# AD7173.net
KiCad netlist of a schematic drawn in EAGLE
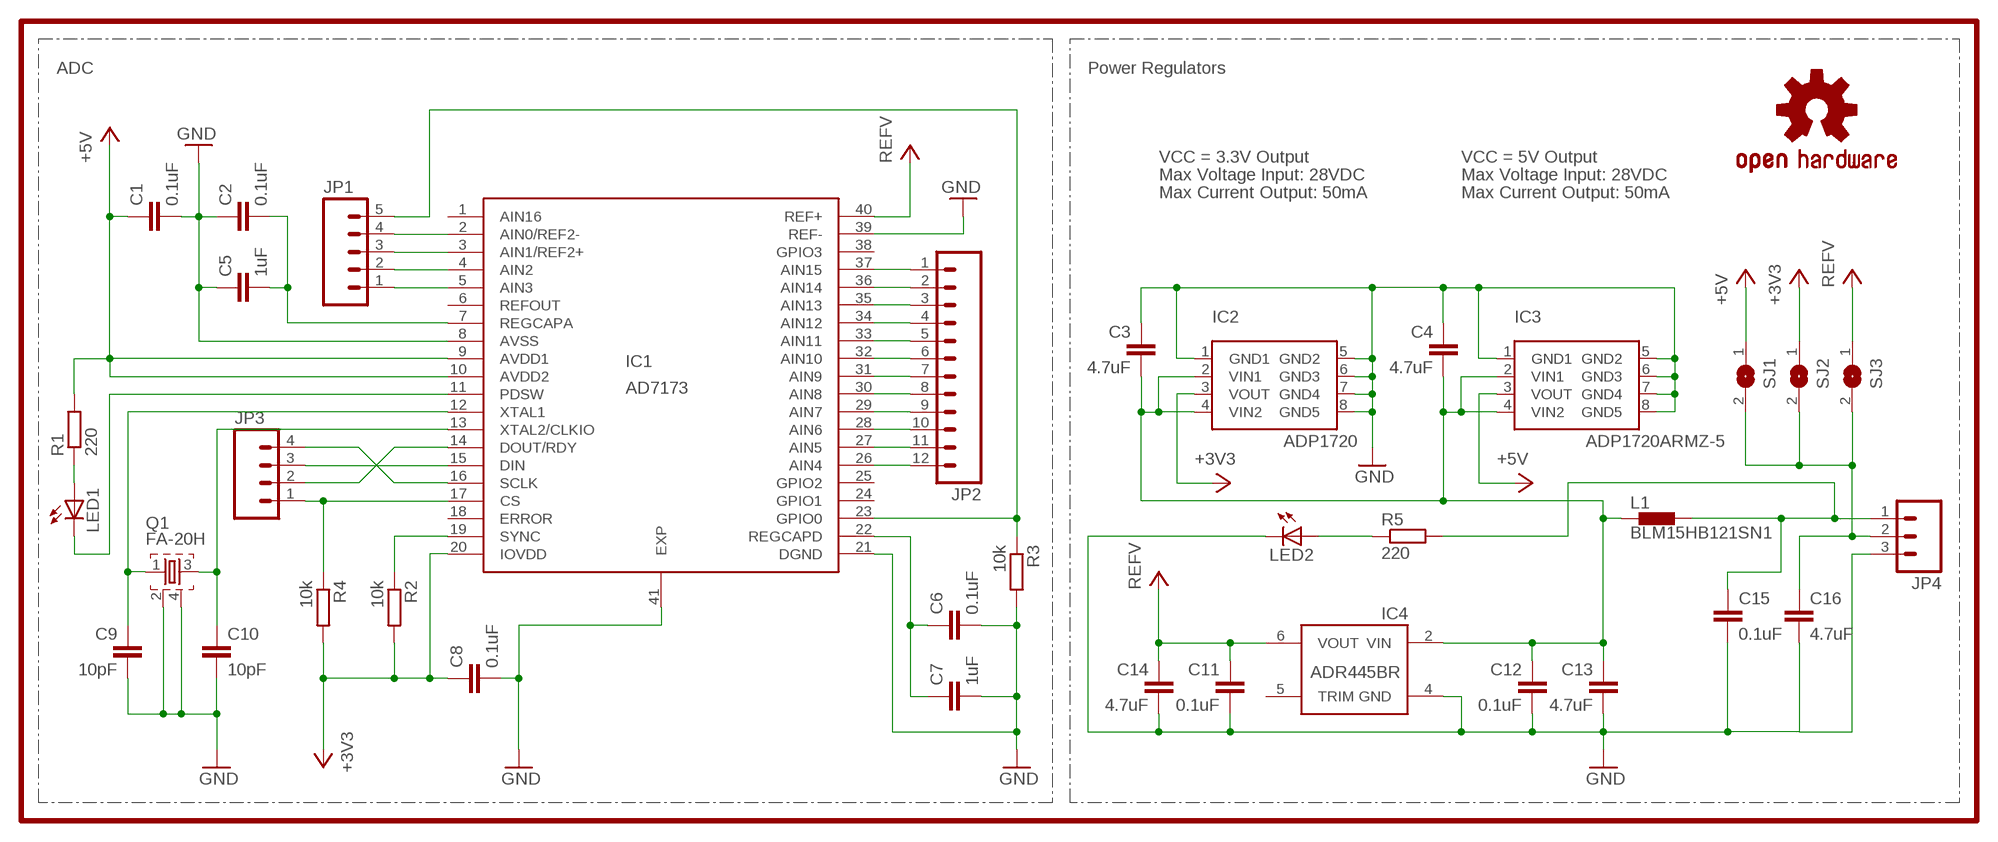
[diagram p0: schematic, sheet 1]

(export (version "E")
  (design (tool "Eeschema 10.0.6"))
  (components
    (comp (ref "C1")
      (value "0.1uF")
      (footprint "eagle-import:C0402")
      (libsource (lib "eagle-import") (part "C-EUC0402"))
    )
    (comp (ref "C2")
      (value "0.1uF")
      (footprint "eagle-import:C0402")
      (libsource (lib "eagle-import") (part "C-EUC0402"))
    )
    (comp (ref "C3")
      (value "4.7uF")
      (footprint "eagle-import:C0402")
      (libsource (lib "eagle-import") (part "C-EUC0402"))
    )
    (comp (ref "C4")
      (value "4.7uF")
      (footprint "eagle-import:C0402")
      (libsource (lib "eagle-import") (part "C-EUC0402"))
    )
    (comp (ref "C5")
      (value "1uF")
      (footprint "eagle-import:C0402")
      (libsource (lib "eagle-import") (part "C-EUC0402"))
    )
    (comp (ref "C6")
      (value "0.1uF")
      (footprint "eagle-import:C0402")
      (libsource (lib "eagle-import") (part "C-EUC0402"))
    )
    (comp (ref "C7")
      (value "1uF")
      (footprint "eagle-import:C0402")
      (libsource (lib "eagle-import") (part "C-EUC0402"))
    )
    (comp (ref "C8")
      (value "0.1uF")
      (footprint "eagle-import:C0402")
      (libsource (lib "eagle-import") (part "C-EUC0402"))
    )
    (comp (ref "C9")
      (value "10pF")
      (footprint "eagle-import:C0402")
      (libsource (lib "eagle-import") (part "C-EUC0402"))
    )
    (comp (ref "C10")
      (value "10pF")
      (footprint "eagle-import:C0402")
      (libsource (lib "eagle-import") (part "C-EUC0402"))
    )
    (comp (ref "C11")
      (value "0.1uF")
      (footprint "eagle-import:C0402")
      (libsource (lib "eagle-import") (part "C-EUC0402"))
    )
    (comp (ref "C12")
      (value "0.1uF")
      (footprint "eagle-import:C0402")
      (libsource (lib "eagle-import") (part "C-EUC0402"))
    )
    (comp (ref "C13")
      (value "4.7uF")
      (footprint "eagle-import:C0402")
      (libsource (lib "eagle-import") (part "C-EUC0402"))
    )
    (comp (ref "C14")
      (value "4.7uF")
      (footprint "eagle-import:C0402")
      (libsource (lib "eagle-import") (part "C-EUC0402"))
    )
    (comp (ref "C15")
      (value "0.1uF")
      (footprint "eagle-import:C0402")
      (libsource (lib "eagle-import") (part "C-EUC0402"))
    )
    (comp (ref "C16")
      (value "4.7uF")
      (footprint "eagle-import:C0402")
      (libsource (lib "eagle-import") (part "C-EUC0402"))
    )
    (comp (ref "IC1")
      (value "AD7173")
      (footprint "eagle-import:LFCSP_WQ6X6MM")
      (fields (field (name "MPN") "MRF24J40-I/ML"))
      (libsource (lib "eagle-import") (part "AD7173"))
    )
    (comp (ref "IC2")
      (value "ADP1720")
      (footprint "eagle-import:MSOP08")
      (libsource (lib "eagle-import") (part "POWER"))
    )
    (comp (ref "IC3")
      (value "ADP1720ARMZ-5")
      (footprint "eagle-import:MSOP08")
      (libsource (lib "eagle-import") (part "POWER"))
    )
    (comp (ref "IC4")
      (value "ADR445BR")
      (footprint "eagle-import:SO8")
      (libsource (lib "eagle-import") (part "ADR44R5B"))
    )
    (comp (ref "JP1")
      (value "M05PTH")
      (footprint "eagle-import:1X05")
      (libsource (lib "eagle-import") (part "M05PTH"))
    )
    (comp (ref "JP2")
      (value "M12PTH")
      (footprint "eagle-import:1X12")
      (libsource (lib "eagle-import") (part "M12PTH"))
    )
    (comp (ref "JP3")
      (value "M04PTH")
      (footprint "eagle-import:1X04")
      (libsource (lib "eagle-import") (part "M04PTH"))
    )
    (comp (ref "JP4")
      (value "M03PTH")
      (footprint "eagle-import:1X03")
      (libsource (lib "eagle-import") (part "M03PTH"))
    )
    (comp (ref "L1")
      (value "BLM15HB121SN1")
      (footprint "eagle-import:0402")
      (libsource (lib "eagle-import") (part "BLM15HB121SN1"))
    )
    (comp (ref "LED1")
      (value "LEDCHIP-LED0603")
      (footprint "eagle-import:CHIP-LED0603")
      (libsource (lib "eagle-import") (part "LEDCHIP-LED0603"))
    )
    (comp (ref "LED2")
      (value "LEDCHIP-LED0603")
      (footprint "eagle-import:CHIP-LED0603")
      (libsource (lib "eagle-import") (part "LEDCHIP-LED0603"))
    )
    (comp (ref "LOGO1")
      (value "OSHW-LOGOS")
      (footprint "eagle-import:OSHW-LOGO-S")
      (libsource (lib "eagle-import") (part "OSHW-LOGOS"))
    )
    (comp (ref "Q1")
      (value "FA-20H")
      (footprint "eagle-import:FA-20H")
      (libsource (lib "eagle-import") (part "FA-20H"))
    )
    (comp (ref "R1")
      (value "220")
      (footprint "eagle-import:R0402")
      (libsource (lib "eagle-import") (part "R-EU_R0402"))
    )
    (comp (ref "R2")
      (value "10k")
      (footprint "eagle-import:R0402")
      (libsource (lib "eagle-import") (part "R-EU_R0402"))
    )
    (comp (ref "R3")
      (value "10k")
      (footprint "eagle-import:R0402")
      (libsource (lib "eagle-import") (part "R-EU_R0402"))
    )
    (comp (ref "R4")
      (value "10k")
      (footprint "eagle-import:R0402")
      (libsource (lib "eagle-import") (part "R-EU_R0402"))
    )
    (comp (ref "R5")
      (value "220")
      (footprint "eagle-import:R0402")
      (libsource (lib "eagle-import") (part "R-EU_R0402"))
    )
    (comp (ref "SJ1") (value "SJ") (footprint "eagle-import:SJ") (libsource (lib "eagle-import") (part "SJ")))
    (comp (ref "SJ2") (value "SJ") (footprint "eagle-import:SJ") (libsource (lib "eagle-import") (part "SJ")))
    (comp (ref "SJ3") (value "SJ") (footprint "eagle-import:SJ") (libsource (lib "eagle-import") (part "SJ")))
  )
  (nets
    (net (code "1") (name "+3V3") (class "Default")
      (node (ref "C8") (pin "1") (pinfunction "1_1") (pintype "passive"))
      (node (ref "IC1") (pin "20") (pinfunction "IOVDD_20") (pintype "input"))
      (node (ref "IC2") (pin "3") (pinfunction "VOUT_3") (pintype "output"))
      (node (ref "R2") (pin "2") (pinfunction "2_2") (pintype "passive"))
      (node (ref "R4") (pin "2") (pinfunction "2_2") (pintype "passive"))
      (node (ref "SJ2") (pin "1") (pinfunction "1_1") (pintype "passive"))
    )
    (net (code "2") (name "+5V") (class "Default")
      (node (ref "C1") (pin "1") (pinfunction "1_1") (pintype "passive"))
      (node (ref "IC1") (pin "10") (pinfunction "AVDD2_10") (pintype "input"))
      (node (ref "IC1") (pin "9") (pinfunction "AVDD1_9") (pintype "input"))
      (node (ref "IC3") (pin "3") (pinfunction "VOUT_3") (pintype "output"))
      (node (ref "R1") (pin "2") (pinfunction "2_2") (pintype "passive"))
      (node (ref "SJ1") (pin "1") (pinfunction "1_1") (pintype "passive"))
    )
    (net (code "3") (name "GND") (class "Default")
      (node (ref "C1") (pin "2") (pinfunction "2_2") (pintype "passive"))
      (node (ref "C10") (pin "2") (pinfunction "2_2") (pintype "passive"))
      (node (ref "C11") (pin "2") (pinfunction "2_2") (pintype "passive"))
      (node (ref "C12") (pin "2") (pinfunction "2_2") (pintype "passive"))
      (node (ref "C13") (pin "2") (pinfunction "2_2") (pintype "passive"))
      (node (ref "C14") (pin "2") (pinfunction "2_2") (pintype "passive"))
      (node (ref "C15") (pin "2") (pinfunction "2_2") (pintype "passive"))
      (node (ref "C16") (pin "2") (pinfunction "2_2") (pintype "passive"))
      (node (ref "C2") (pin "1") (pinfunction "1_1") (pintype "passive"))
      (node (ref "C3") (pin "1") (pinfunction "1_1") (pintype "passive"))
      (node (ref "C4") (pin "1") (pinfunction "1_1") (pintype "passive"))
      (node (ref "C5") (pin "1") (pinfunction "1_1") (pintype "passive"))
      (node (ref "C6") (pin "2") (pinfunction "2_2") (pintype "passive"))
      (node (ref "C7") (pin "2") (pinfunction "2_2") (pintype "passive"))
      (node (ref "C8") (pin "2") (pinfunction "2_2") (pintype "passive"))
      (node (ref "C9") (pin "2") (pinfunction "2_2") (pintype "passive"))
      (node (ref "IC1") (pin "21") (pinfunction "DGND_21") (pintype "input"))
      (node (ref "IC1") (pin "39") (pinfunction "REF-_39") (pintype "input"))
      (node (ref "IC1") (pin "41") (pinfunction "EXP_41") (pintype "output"))
      (node (ref "IC1") (pin "8") (pinfunction "AVSS_8") (pintype "input"))
      (node (ref "IC2") (pin "1") (pinfunction "GND1_1") (pintype "power_in"))
      (node (ref "IC2") (pin "5") (pinfunction "GND2_5") (pintype "power_in"))
      (node (ref "IC2") (pin "6") (pinfunction "GND3_6") (pintype "power_in"))
      (node (ref "IC2") (pin "7") (pinfunction "GND4_7") (pintype "power_in"))
      (node (ref "IC2") (pin "8") (pinfunction "GND5_8") (pintype "power_in"))
      (node (ref "IC3") (pin "1") (pinfunction "GND1_1") (pintype "power_in"))
      (node (ref "IC3") (pin "5") (pinfunction "GND2_5") (pintype "power_in"))
      (node (ref "IC3") (pin "6") (pinfunction "GND3_6") (pintype "power_in"))
      (node (ref "IC3") (pin "7") (pinfunction "GND4_7") (pintype "power_in"))
      (node (ref "IC3") (pin "8") (pinfunction "GND5_8") (pintype "power_in"))
      (node (ref "IC4") (pin "4") (pinfunction "GND_4") (pintype "power_in"))
      (node (ref "JP4") (pin "3") (pinfunction "3_3") (pintype "passive"))
      (node (ref "LED2") (pin "C") (pinfunction "C_C") (pintype "passive"))
      (node (ref "Q1") (pin "2") (pinfunction "2_2") (pintype "passive"))
      (node (ref "Q1") (pin "4") (pinfunction "4_4") (pintype "passive"))
      (node (ref "R3") (pin "2") (pinfunction "2_2") (pintype "passive"))
    )
    (net (code "4") (name "Net-(C15-Pad1)") (class "Default")
      (node (ref "C15") (pin "1") (pinfunction "1_1") (pintype "passive"))
      (node (ref "JP4") (pin "1") (pinfunction "1_1") (pintype "passive"))
      (node (ref "L1") (pin "2") (pinfunction "2_2") (pintype "passive"))
      (node (ref "R5") (pin "2") (pinfunction "2_2") (pintype "passive"))
    )
    (net (code "5") (name "Net-(C16-Pad1)") (class "Default")
      (node (ref "C16") (pin "1") (pinfunction "1_1") (pintype "passive"))
      (node (ref "JP4") (pin "2") (pinfunction "2_2") (pintype "passive"))
      (node (ref "SJ1") (pin "2") (pinfunction "2_2") (pintype "passive"))
      (node (ref "SJ2") (pin "2") (pinfunction "2_2") (pintype "passive"))
      (node (ref "SJ3") (pin "2") (pinfunction "2_2") (pintype "passive"))
    )
    (net (code "6") (name "Net-(IC1-AIN0{slash}REF2-)") (class "Default")
      (node (ref "IC1") (pin "2") (pinfunction "AIN0/REF2-_2") (pintype "input"))
      (node (ref "JP1") (pin "4") (pinfunction "4_4") (pintype "passive"))
    )
    (net (code "7") (name "Net-(IC1-AIN1{slash}REF2+)") (class "Default")
      (node (ref "IC1") (pin "3") (pinfunction "AIN1/REF2+_3") (pintype "input"))
      (node (ref "JP1") (pin "3") (pinfunction "3_3") (pintype "passive"))
    )
    (net (code "8") (name "Net-(IC1-AIN2)") (class "Default")
      (node (ref "IC1") (pin "4") (pinfunction "AIN2_4") (pintype "input"))
      (node (ref "JP1") (pin "2") (pinfunction "2_2") (pintype "passive"))
    )
    (net (code "9") (name "Net-(IC1-AIN3)") (class "Default")
      (node (ref "IC1") (pin "5") (pinfunction "AIN3_5") (pintype "input"))
      (node (ref "JP1") (pin "1") (pinfunction "1_1") (pintype "passive"))
    )
    (net (code "10") (name "Net-(IC1-AIN4)") (class "Default")
      (node (ref "IC1") (pin "26") (pinfunction "AIN4_26") (pintype "input"))
      (node (ref "JP2") (pin "12") (pinfunction "12_12") (pintype "passive"))
    )
    (net (code "11") (name "Net-(IC1-AIN5)") (class "Default")
      (node (ref "IC1") (pin "27") (pinfunction "AIN5_27") (pintype "input"))
      (node (ref "JP2") (pin "11") (pinfunction "11_11") (pintype "passive"))
    )
    (net (code "12") (name "Net-(IC1-AIN6)") (class "Default")
      (node (ref "IC1") (pin "28") (pinfunction "AIN6_28") (pintype "input"))
      (node (ref "JP2") (pin "10") (pinfunction "10_10") (pintype "passive"))
    )
    (net (code "13") (name "Net-(IC1-AIN7)") (class "Default")
      (node (ref "IC1") (pin "29") (pinfunction "AIN7_29") (pintype "input"))
      (node (ref "JP2") (pin "9") (pinfunction "9_9") (pintype "passive"))
    )
    (net (code "14") (name "Net-(IC1-AIN8)") (class "Default")
      (node (ref "IC1") (pin "30") (pinfunction "AIN8_30") (pintype "input"))
      (node (ref "JP2") (pin "8") (pinfunction "8_8") (pintype "passive"))
    )
    (net (code "15") (name "Net-(IC1-AIN9)") (class "Default")
      (node (ref "IC1") (pin "31") (pinfunction "AIN9_31") (pintype "input"))
      (node (ref "JP2") (pin "7") (pinfunction "7_7") (pintype "passive"))
    )
    (net (code "16") (name "Net-(IC1-AIN10)") (class "Default")
      (node (ref "IC1") (pin "32") (pinfunction "AIN10_32") (pintype "input"))
      (node (ref "JP2") (pin "6") (pinfunction "6_6") (pintype "passive"))
    )
    (net (code "17") (name "Net-(IC1-AIN11)") (class "Default")
      (node (ref "IC1") (pin "33") (pinfunction "AIN11_33") (pintype "input"))
      (node (ref "JP2") (pin "5") (pinfunction "5_5") (pintype "passive"))
    )
    (net (code "18") (name "Net-(IC1-AIN12)") (class "Default")
      (node (ref "IC1") (pin "34") (pinfunction "AIN12_34") (pintype "input"))
      (node (ref "JP2") (pin "4") (pinfunction "4_4") (pintype "passive"))
    )
    (net (code "19") (name "Net-(IC1-AIN13)") (class "Default")
      (node (ref "IC1") (pin "35") (pinfunction "AIN13_35") (pintype "input"))
      (node (ref "JP2") (pin "3") (pinfunction "3_3") (pintype "passive"))
    )
    (net (code "20") (name "Net-(IC1-AIN14)") (class "Default")
      (node (ref "IC1") (pin "36") (pinfunction "AIN14_36") (pintype "input"))
      (node (ref "JP2") (pin "2") (pinfunction "2_2") (pintype "passive"))
    )
    (net (code "21") (name "Net-(IC1-AIN15)") (class "Default")
      (node (ref "IC1") (pin "37") (pinfunction "AIN15_37") (pintype "input"))
      (node (ref "JP2") (pin "1") (pinfunction "1_1") (pintype "passive"))
    )
    (net (code "22") (name "Net-(IC1-CS)") (class "Default")
      (node (ref "IC1") (pin "17") (pinfunction "CS_17") (pintype "input"))
      (node (ref "JP3") (pin "1") (pinfunction "1_1") (pintype "passive"))
      (node (ref "R4") (pin "1") (pinfunction "1_1") (pintype "passive"))
    )
    (net (code "23") (name "Net-(IC1-DIN)") (class "Default")
      (node (ref "IC1") (pin "15") (pinfunction "DIN_15") (pintype "input"))
      (node (ref "JP3") (pin "3") (pinfunction "3_3") (pintype "passive"))
    )
    (net (code "24") (name "Net-(IC1-DOUT{slash}RDY)") (class "Default")
      (node (ref "IC1") (pin "14") (pinfunction "DOUT/RDY_14") (pintype "output"))
      (node (ref "JP3") (pin "2") (pinfunction "2_2") (pintype "passive"))
    )
    (net (code "25") (name "Net-(IC1-GPIO0)") (class "Default")
      (node (ref "IC1") (pin "23") (pinfunction "GPIO0_23") (pintype "bidirectional"))
      (node (ref "JP1") (pin "5") (pinfunction "5_5") (pintype "passive"))
      (node (ref "R3") (pin "1") (pinfunction "1_1") (pintype "passive"))
    )
    (net (code "26") (name "Net-(IC1-PDSW)") (class "Default")
      (node (ref "IC1") (pin "11") (pinfunction "PDSW_11") (pintype "input"))
      (node (ref "LED1") (pin "C") (pinfunction "C_C") (pintype "passive"))
    )
    (net (code "27") (name "Net-(IC1-REGCAPA)") (class "Default")
      (node (ref "C2") (pin "2") (pinfunction "2_2") (pintype "passive"))
      (node (ref "C5") (pin "2") (pinfunction "2_2") (pintype "passive"))
      (node (ref "IC1") (pin "7") (pinfunction "REGCAPA_7") (pintype "input"))
    )
    (net (code "28") (name "Net-(IC1-REGCAPD)") (class "Default")
      (node (ref "C6") (pin "1") (pinfunction "1_1") (pintype "passive"))
      (node (ref "C7") (pin "1") (pinfunction "1_1") (pintype "passive"))
      (node (ref "IC1") (pin "22") (pinfunction "REGCAPD_22") (pintype "input"))
    )
    (net (code "29") (name "Net-(IC1-SCLK)") (class "Default")
      (node (ref "IC1") (pin "16") (pinfunction "SCLK_16") (pintype "input"))
      (node (ref "JP3") (pin "4") (pinfunction "4_4") (pintype "passive"))
    )
    (net (code "30") (name "Net-(IC1-SYNC)") (class "Default")
      (node (ref "IC1") (pin "19") (pinfunction "SYNC_19") (pintype "input"))
      (node (ref "R2") (pin "1") (pinfunction "1_1") (pintype "passive"))
    )
    (net (code "31") (name "Net-(IC1-XTAL1)") (class "Default")
      (node (ref "C9") (pin "1") (pinfunction "1_1") (pintype "passive"))
      (node (ref "IC1") (pin "12") (pinfunction "XTAL1_12") (pintype "input"))
      (node (ref "Q1") (pin "1") (pinfunction "1_1") (pintype "passive"))
    )
    (net (code "32") (name "Net-(IC1-XTAL2{slash}CLKIO)") (class "Default")
      (node (ref "C10") (pin "1") (pinfunction "1_1") (pintype "passive"))
      (node (ref "IC1") (pin "13") (pinfunction "XTAL2/CLKIO_13") (pintype "input"))
      (node (ref "Q1") (pin "3") (pinfunction "3_3") (pintype "passive"))
    )
    (net (code "33") (name "Net-(IC2-VIN1)") (class "Default")
      (node (ref "C12") (pin "1") (pinfunction "1_1") (pintype "passive"))
      (node (ref "C13") (pin "1") (pinfunction "1_1") (pintype "passive"))
      (node (ref "C3") (pin "2") (pinfunction "2_2") (pintype "passive"))
      (node (ref "C4") (pin "2") (pinfunction "2_2") (pintype "passive"))
      (node (ref "IC2") (pin "2") (pinfunction "VIN1_2") (pintype "input"))
      (node (ref "IC2") (pin "4") (pinfunction "VIN2_4") (pintype "input"))
      (node (ref "IC3") (pin "2") (pinfunction "VIN1_2") (pintype "input"))
      (node (ref "IC3") (pin "4") (pinfunction "VIN2_4") (pintype "input"))
      (node (ref "IC4") (pin "2") (pinfunction "VIN_2") (pintype "power_in"))
      (node (ref "L1") (pin "1") (pinfunction "1_1") (pintype "passive"))
    )
    (net (code "34") (name "Net-(LED1-PadA)") (class "Default")
      (node (ref "LED1") (pin "A") (pinfunction "A_A") (pintype "passive"))
      (node (ref "R1") (pin "1") (pinfunction "1_1") (pintype "passive"))
    )
    (net (code "35") (name "Net-(LED2-PadA)") (class "Default")
      (node (ref "LED2") (pin "A") (pinfunction "A_A") (pintype "passive"))
      (node (ref "R5") (pin "1") (pinfunction "1_1") (pintype "passive"))
    )
    (net (code "36") (name "REFV") (class "Default")
      (node (ref "C11") (pin "1") (pinfunction "1_1") (pintype "passive"))
      (node (ref "C14") (pin "1") (pinfunction "1_1") (pintype "passive"))
      (node (ref "IC1") (pin "40") (pinfunction "REF+_40") (pintype "input"))
      (node (ref "IC4") (pin "6") (pinfunction "VOUT_6") (pintype "bidirectional"))
      (node (ref "SJ3") (pin "1") (pinfunction "1_1") (pintype "passive"))
    )
    (net (code "37") (name "unconnected-(IC1-AIN16-Pad1)") (class "Default")
      (node (ref "IC1") (pin "1") (pinfunction "AIN16_1") (pintype "input"))
    )
    (net (code "38") (name "unconnected-(IC1-ERROR-Pad18)") (class "Default")
      (node (ref "IC1") (pin "18") (pinfunction "ERROR_18") (pintype "input"))
    )
    (net (code "39") (name "unconnected-(IC1-GPIO1-Pad24)") (class "Default")
      (node (ref "IC1") (pin "24") (pinfunction "GPIO1_24") (pintype "bidirectional"))
    )
    (net (code "40") (name "unconnected-(IC1-GPIO2-Pad25)") (class "Default")
      (node (ref "IC1") (pin "25") (pinfunction "GPIO2_25") (pintype "bidirectional"))
    )
    (net (code "41") (name "unconnected-(IC1-GPIO3-Pad38)") (class "Default")
      (node (ref "IC1") (pin "38") (pinfunction "GPIO3_38") (pintype "bidirectional"))
    )
    (net (code "42") (name "unconnected-(IC1-REFOUT-Pad6)") (class "Default")
      (node (ref "IC1") (pin "6") (pinfunction "REFOUT_6") (pintype "output"))
    )
    (net (code "43") (name "unconnected-(IC4-TRIM-Pad5)") (class "Default")
      (node (ref "IC4") (pin "5") (pinfunction "TRIM_5") (pintype "bidirectional"))
    )
  )
)
